# SMP_Project_2.net
KiCad netlist of a schematic drawn in EasyEDA Pro
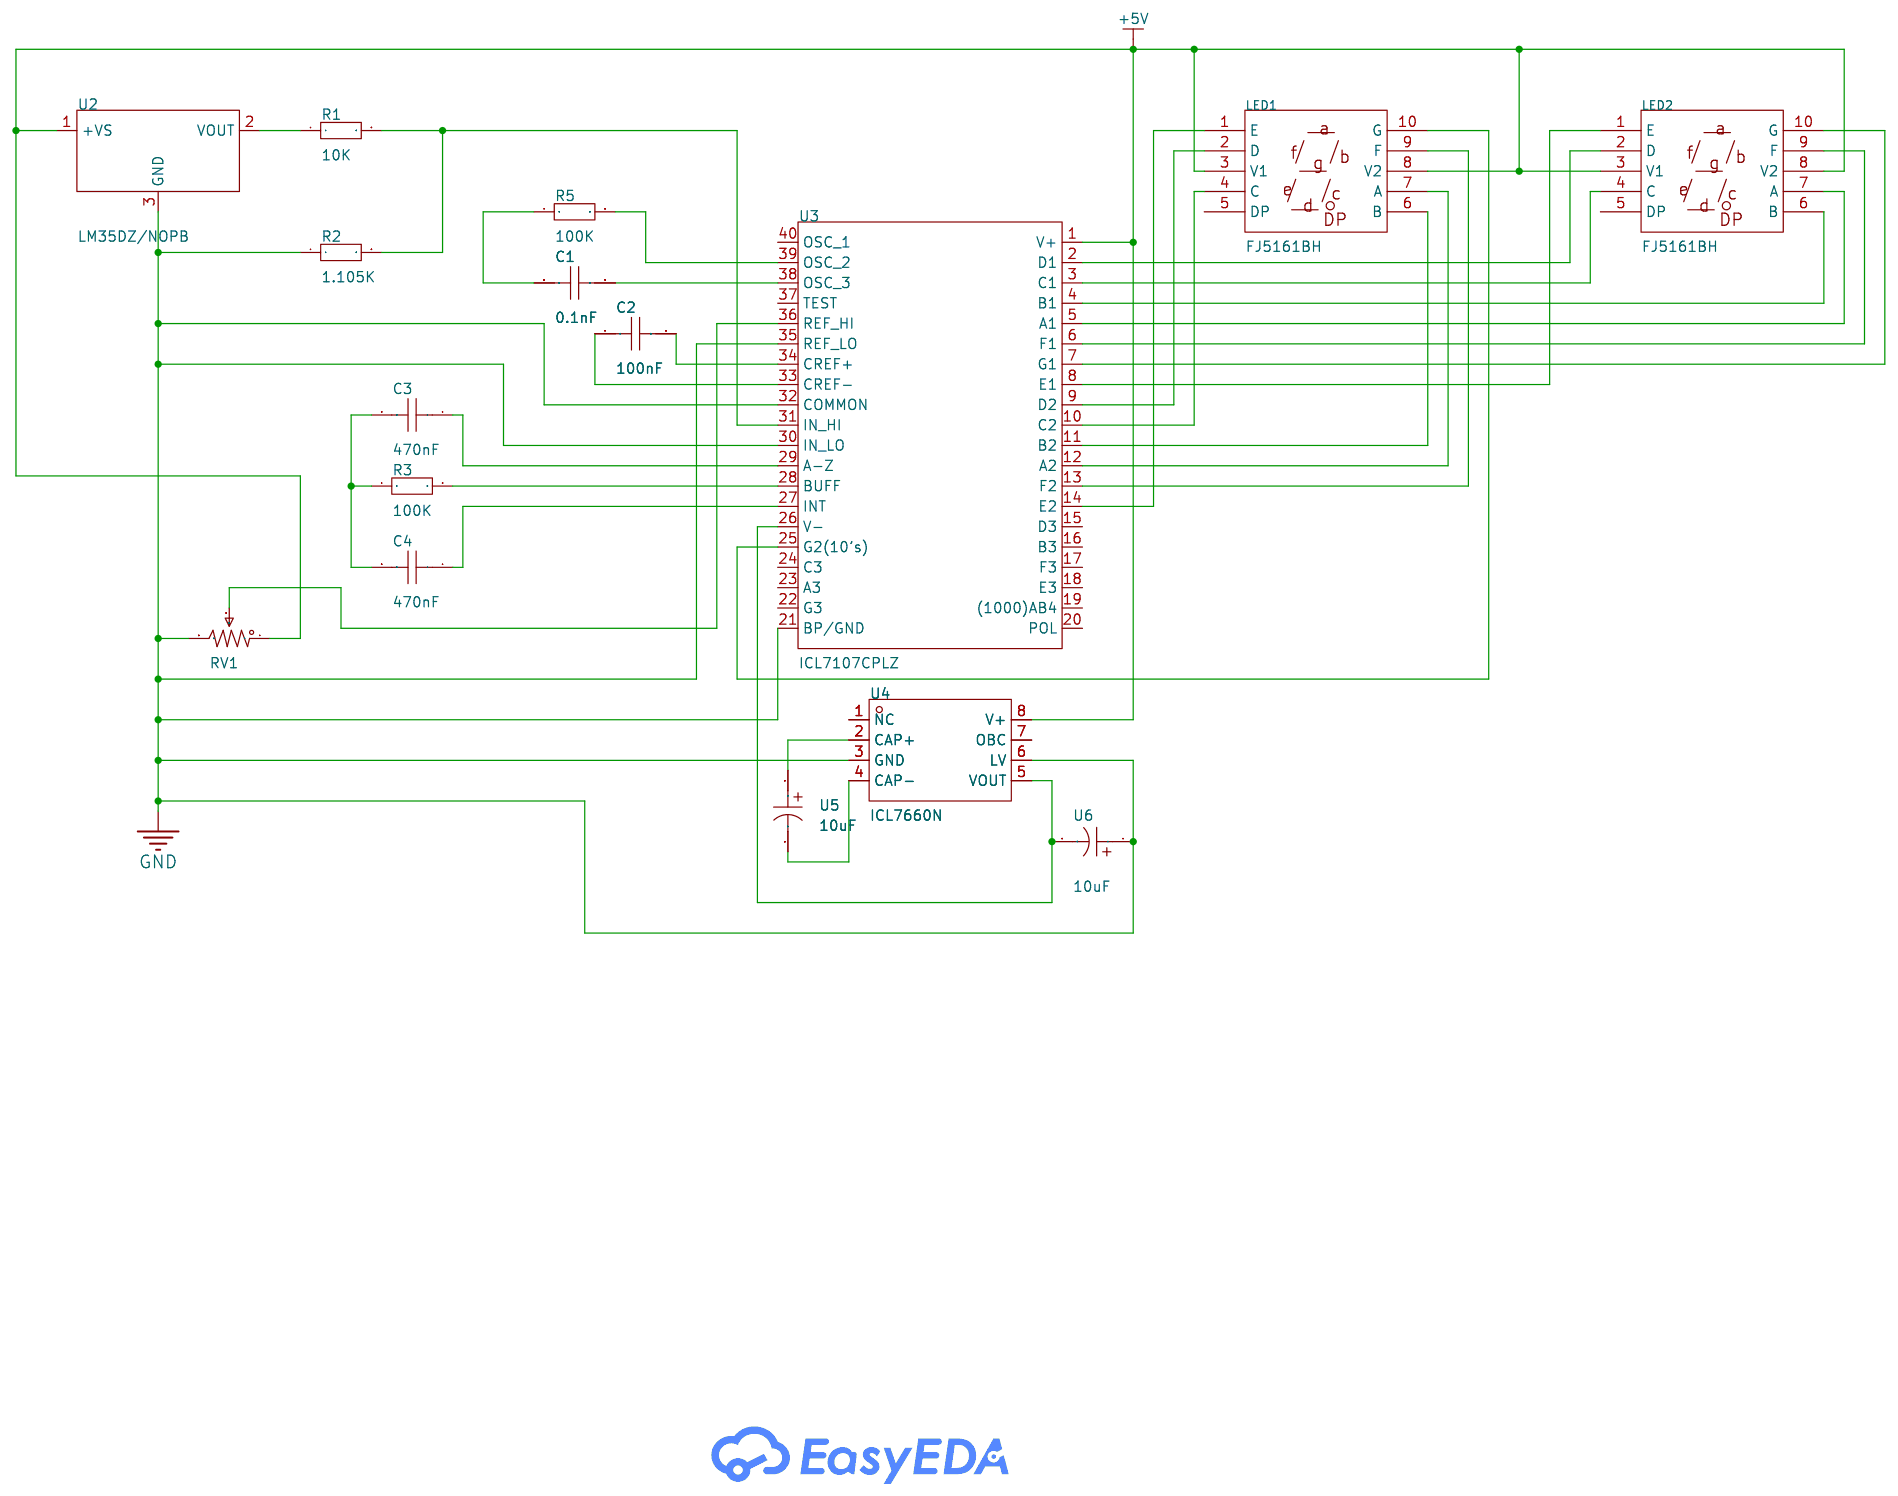
[diagram p0: schematic sheet]

(export (version "E")
  (design (tool "Eeschema 10.0.6"))
  (components
    (comp (ref "C1")
      (value "0.1nF")
      (footprint "easyedapro:C0805")
      (libsource (lib "easyedapro") (part "CAP"))
    )
    (comp (ref "C2")
      (value "100nF")
      (footprint "easyedapro:C0805")
      (libsource (lib "easyedapro") (part "CAP"))
    )
    (comp (ref "C3")
      (value "470nF")
      (footprint "easyedapro:C0805")
      (libsource (lib "easyedapro") (part "CAP"))
    )
    (comp (ref "C4")
      (value "470nF")
      (footprint "easyedapro:C0805")
      (libsource (lib "easyedapro") (part "CAP"))
    )
    (comp (ref "LED1")
      (value "FJ5161BH")
      (footprint "easyedapro:LED-SEG-TH_FJ5161BH")
      (fields (field (name "Manufacturer") "志浩"))
      (libsource (lib "easyedapro") (part "FJ5161BH"))
    )
    (comp (ref "LED2")
      (value "FJ5161BH")
      (footprint "easyedapro:LED-SEG-TH_FJ5161BH")
      (fields (field (name "Manufacturer") "志浩"))
      (libsource (lib "easyedapro") (part "FJ5161BH"))
    )
    (comp (ref "R1") (value "10K") (footprint "easyedapro:R0603") (libsource (lib "easyedapro") (part "Res")))
    (comp (ref "R2")
      (value "1.105K")
      (footprint "easyedapro:R0603")
      (libsource (lib "easyedapro") (part "Res"))
    )
    (comp (ref "R3")
      (value "100K")
      (footprint "easyedapro:R0603")
      (libsource (lib "easyedapro") (part "Res"))
    )
    (comp (ref "R5")
      (value "100K")
      (footprint "easyedapro:R0603")
      (libsource (lib "easyedapro") (part "Res"))
    )
    (comp (ref "RV1")
      (value "1kΩ")
      (footprint "easyedapro:RES-ADJ-TH_3P-L10.0-W10.0-P2.50-BL-BS")
      (fields (field (name "Manufacturer Part") "3296W-1-102") (field (name "Manufacturer") "BOCHEN(博晨)"))
      (libsource (lib "easyedapro") (part "3296W-1-102"))
    )
    (comp (ref "U2")
      (value "LM35DZ/NOPB")
      (footprint "easyedapro:TO-92-3_L4.9-W3.7-P1.27-L")
      (fields (field (name "Manufacturer") "TI(德州仪器)"))
      (libsource (lib "easyedapro") (part "LM35DZ"))
    )
    (comp (ref "U3")
      (value "ICL7107CPLZ")
      (footprint "easyedapro:DIP-40_L52.3-W13.9-P2.54-LS15.2-BL")
      (fields (field (name "Manufacturer") "RENESAS(瑞萨)/IDT"))
      (libsource (lib "easyedapro") (part "ICL7107CPLZ_C1520744"))
    )
    (comp (ref "U4")
      (value "ICL7660N")
      (footprint "easyedapro:DIP-8_L9.4-W6.4-P2.54-LS9.1-BL")
      (fields (field (name "Manufacturer") "HGSEMI(华冠)"))
      (libsource (lib "easyedapro") (part "ICL7660N"))
    )
    (comp (ref "U5")
      (value "10uF")
      (footprint "easyedapro:CAP-TH_BD10.0-P5.00-D0.6-FD")
      (libsource (lib "easyedapro") (part "10UF_400V"))
    )
    (comp (ref "U6")
      (value "10uF")
      (footprint "easyedapro:CAP-TH_BD10.0-P5.00-D0.6-FD")
      (libsource (lib "easyedapro") (part "10UF_400V"))
    )
  )
  (nets
    (net (code "1") (name "+5V") (class "Default")
      (node (ref "LED1") (pin "3") (pinfunction "V1_3") (pintype "input"))
      (node (ref "LED1") (pin "8") (pinfunction "V2_8") (pintype "input"))
      (node (ref "LED2") (pin "3") (pinfunction "V1_3") (pintype "input"))
      (node (ref "LED2") (pin "8") (pinfunction "V2_8") (pintype "input"))
      (node (ref "RV1") (pin "1") (pinfunction "1_1") (pintype "input"))
      (node (ref "U2") (pin "1") (pinfunction "+VS_1") (pintype "unspecified"))
      (node (ref "U3") (pin "1") (pinfunction "V+_1") (pintype "unspecified"))
      (node (ref "U4") (pin "8") (pinfunction "V+_8") (pintype "unspecified"))
    )
    (net (code "2") (name "GND") (class "Default")
      (node (ref "R2") (pin "1") (pinfunction "1_1") (pintype "input"))
      (node (ref "RV1") (pin "3") (pinfunction "3_3") (pintype "input"))
      (node (ref "U2") (pin "3") (pinfunction "GND_3") (pintype "unspecified"))
      (node (ref "U3") (pin "21") (pinfunction "BP/GND_21") (pintype "unspecified"))
      (node (ref "U3") (pin "30") (pinfunction "IN_LO_30") (pintype "unspecified"))
      (node (ref "U3") (pin "32") (pinfunction "COMMON_32") (pintype "unspecified"))
      (node (ref "U3") (pin "35") (pinfunction "REF_LO_35") (pintype "unspecified"))
      (node (ref "U4") (pin "3") (pinfunction "GND_3") (pintype "unspecified"))
      (node (ref "U4") (pin "6") (pinfunction "LV_6") (pintype "unspecified"))
      (node (ref "U6") (pin "1") (pinfunction "1_1") (pintype "input"))
    )
    (net (code "3") (name "Net-(C1-Pad2)") (class "Default")
      (node (ref "C1") (pin "2") (pinfunction "2_2") (pintype "input"))
      (node (ref "R5") (pin "1") (pinfunction "1_1") (pintype "input"))
    )
    (net (code "4") (name "Net-(C3-Pad2)") (class "Default")
      (node (ref "C3") (pin "2") (pinfunction "2_2") (pintype "input"))
      (node (ref "C4") (pin "2") (pinfunction "2_2") (pintype "input"))
      (node (ref "R3") (pin "1") (pinfunction "1_1") (pintype "input"))
    )
    (net (code "5") (name "Net-(LED1-A)") (class "Default")
      (node (ref "LED1") (pin "7") (pinfunction "A_7") (pintype "input"))
      (node (ref "U3") (pin "12") (pinfunction "A2_12") (pintype "unspecified"))
    )
    (net (code "6") (name "Net-(LED1-B)") (class "Default")
      (node (ref "LED1") (pin "6") (pinfunction "B_6") (pintype "input"))
      (node (ref "U3") (pin "11") (pinfunction "B2_11") (pintype "unspecified"))
    )
    (net (code "7") (name "Net-(LED1-C)") (class "Default")
      (node (ref "LED1") (pin "4") (pinfunction "C_4") (pintype "input"))
      (node (ref "U3") (pin "10") (pinfunction "C2_10") (pintype "unspecified"))
    )
    (net (code "8") (name "Net-(LED1-D)") (class "Default")
      (node (ref "LED1") (pin "2") (pinfunction "D_2") (pintype "input"))
      (node (ref "U3") (pin "9") (pinfunction "D2_9") (pintype "unspecified"))
    )
    (net (code "9") (name "Net-(LED1-E)") (class "Default")
      (node (ref "LED1") (pin "1") (pinfunction "E_1") (pintype "input"))
      (node (ref "U3") (pin "14") (pinfunction "E2_14") (pintype "unspecified"))
    )
    (net (code "10") (name "Net-(LED1-F)") (class "Default")
      (node (ref "LED1") (pin "9") (pinfunction "F_9") (pintype "input"))
      (node (ref "U3") (pin "13") (pinfunction "F2_13") (pintype "unspecified"))
    )
    (net (code "11") (name "Net-(LED1-G)") (class "Default")
      (node (ref "LED1") (pin "10") (pinfunction "G_10") (pintype "input"))
      (node (ref "U3") (pin "25") (pinfunction "G2(10’s)_25") (pintype "unspecified"))
    )
    (net (code "12") (name "Net-(LED2-A)") (class "Default")
      (node (ref "LED2") (pin "7") (pinfunction "A_7") (pintype "input"))
      (node (ref "U3") (pin "5") (pinfunction "A1_5") (pintype "unspecified"))
    )
    (net (code "13") (name "Net-(LED2-B)") (class "Default")
      (node (ref "LED2") (pin "6") (pinfunction "B_6") (pintype "input"))
      (node (ref "U3") (pin "4") (pinfunction "B1_4") (pintype "unspecified"))
    )
    (net (code "14") (name "Net-(LED2-C)") (class "Default")
      (node (ref "LED2") (pin "4") (pinfunction "C_4") (pintype "input"))
      (node (ref "U3") (pin "3") (pinfunction "C1_3") (pintype "unspecified"))
    )
    (net (code "15") (name "Net-(LED2-D)") (class "Default")
      (node (ref "LED2") (pin "2") (pinfunction "D_2") (pintype "input"))
      (node (ref "U3") (pin "2") (pinfunction "D1_2") (pintype "unspecified"))
    )
    (net (code "16") (name "Net-(LED2-E)") (class "Default")
      (node (ref "LED2") (pin "1") (pinfunction "E_1") (pintype "input"))
      (node (ref "U3") (pin "8") (pinfunction "E1_8") (pintype "unspecified"))
    )
    (net (code "17") (name "Net-(LED2-F)") (class "Default")
      (node (ref "LED2") (pin "9") (pinfunction "F_9") (pintype "input"))
      (node (ref "U3") (pin "6") (pinfunction "F1_6") (pintype "unspecified"))
    )
    (net (code "18") (name "Net-(LED2-G)") (class "Default")
      (node (ref "LED2") (pin "10") (pinfunction "G_10") (pintype "input"))
      (node (ref "U3") (pin "7") (pinfunction "G1_7") (pintype "unspecified"))
    )
    (net (code "19") (name "Net-(U2-VOUT)") (class "Default")
      (node (ref "R1") (pin "1") (pinfunction "1_1") (pintype "input"))
      (node (ref "U2") (pin "2") (pinfunction "VOUT_2") (pintype "unspecified"))
    )
    (net (code "20") (name "Net-(U3-A-Z)") (class "Default")
      (node (ref "C3") (pin "1") (pinfunction "1_1") (pintype "input"))
      (node (ref "U3") (pin "29") (pinfunction "A-Z_29") (pintype "unspecified"))
    )
    (net (code "21") (name "Net-(U3-BUFF)") (class "Default")
      (node (ref "R3") (pin "2") (pinfunction "2_2") (pintype "input"))
      (node (ref "U3") (pin "28") (pinfunction "BUFF_28") (pintype "unspecified"))
    )
    (net (code "22") (name "Net-(U3-CREF+)") (class "Default")
      (node (ref "C2") (pin "2") (pinfunction "2_2") (pintype "input"))
      (node (ref "U3") (pin "34") (pinfunction "CREF+_34") (pintype "unspecified"))
    )
    (net (code "23") (name "Net-(U3-CREF-)") (class "Default")
      (node (ref "C2") (pin "1") (pinfunction "1_1") (pintype "input"))
      (node (ref "U3") (pin "33") (pinfunction "CREF-_33") (pintype "unspecified"))
    )
    (net (code "24") (name "Net-(U3-INT)") (class "Default")
      (node (ref "C4") (pin "1") (pinfunction "1_1") (pintype "input"))
      (node (ref "U3") (pin "27") (pinfunction "INT_27") (pintype "unspecified"))
    )
    (net (code "25") (name "Net-(U3-IN_HI)") (class "Default")
      (node (ref "R1") (pin "2") (pinfunction "2_2") (pintype "input"))
      (node (ref "R2") (pin "2") (pinfunction "2_2") (pintype "input"))
      (node (ref "U3") (pin "31") (pinfunction "IN_HI_31") (pintype "unspecified"))
    )
    (net (code "26") (name "Net-(U3-OSC_2)") (class "Default")
      (node (ref "R5") (pin "2") (pinfunction "2_2") (pintype "input"))
      (node (ref "U3") (pin "39") (pinfunction "OSC_2_39") (pintype "unspecified"))
    )
    (net (code "27") (name "Net-(U3-OSC_3)") (class "Default")
      (node (ref "C1") (pin "1") (pinfunction "1_1") (pintype "input"))
      (node (ref "U3") (pin "38") (pinfunction "OSC_3_38") (pintype "unspecified"))
    )
    (net (code "28") (name "Net-(U3-REF_HI)") (class "Default")
      (node (ref "RV1") (pin "2") (pinfunction "2_2") (pintype "input"))
      (node (ref "U3") (pin "36") (pinfunction "REF_HI_36") (pintype "unspecified"))
    )
    (net (code "29") (name "Net-(U3-V-)") (class "Default")
      (node (ref "U3") (pin "26") (pinfunction "V-_26") (pintype "unspecified"))
      (node (ref "U4") (pin "5") (pinfunction "VOUT_5") (pintype "unspecified"))
      (node (ref "U6") (pin "2") (pinfunction "2_2") (pintype "input"))
    )
    (net (code "30") (name "Net-(U4-CAP+)") (class "Default")
      (node (ref "U4") (pin "2") (pinfunction "CAP+_2") (pintype "unspecified"))
      (node (ref "U5") (pin "1") (pinfunction "1_1") (pintype "input"))
    )
    (net (code "31") (name "Net-(U4-CAP-)") (class "Default")
      (node (ref "U4") (pin "4") (pinfunction "CAP-_4") (pintype "unspecified"))
      (node (ref "U5") (pin "2") (pinfunction "2_2") (pintype "input"))
    )
    (net (code "32") (name "unconnected-(LED1-DP-Pad5)") (class "Default")
      (node (ref "LED1") (pin "5") (pinfunction "DP_5") (pintype "input"))
    )
    (net (code "33") (name "unconnected-(LED2-DP-Pad5)") (class "Default")
      (node (ref "LED2") (pin "5") (pinfunction "DP_5") (pintype "input"))
    )
    (net (code "34") (name "unconnected-(U3-(1000)AB4-Pad19)") (class "Default")
      (node (ref "U3") (pin "19") (pinfunction "(1000)AB4_19") (pintype "unspecified"))
    )
    (net (code "35") (name "unconnected-(U3-A3-Pad23)") (class "Default")
      (node (ref "U3") (pin "23") (pinfunction "A3_23") (pintype "unspecified"))
    )
    (net (code "36") (name "unconnected-(U3-B3-Pad16)") (class "Default")
      (node (ref "U3") (pin "16") (pinfunction "B3_16") (pintype "unspecified"))
    )
    (net (code "37") (name "unconnected-(U3-C3-Pad24)") (class "Default")
      (node (ref "U3") (pin "24") (pinfunction "C3_24") (pintype "unspecified"))
    )
    (net (code "38") (name "unconnected-(U3-D3-Pad15)") (class "Default")
      (node (ref "U3") (pin "15") (pinfunction "D3_15") (pintype "unspecified"))
    )
    (net (code "39") (name "unconnected-(U3-E3-Pad18)") (class "Default")
      (node (ref "U3") (pin "18") (pinfunction "E3_18") (pintype "unspecified"))
    )
    (net (code "40") (name "unconnected-(U3-F3-Pad17)") (class "Default")
      (node (ref "U3") (pin "17") (pinfunction "F3_17") (pintype "unspecified"))
    )
    (net (code "41") (name "unconnected-(U3-G3-Pad22)") (class "Default")
      (node (ref "U3") (pin "22") (pinfunction "G3_22") (pintype "unspecified"))
    )
    (net (code "42") (name "unconnected-(U3-OSC_1-Pad40)") (class "Default")
      (node (ref "U3") (pin "40") (pinfunction "OSC_1_40") (pintype "unspecified"))
    )
    (net (code "43") (name "unconnected-(U3-POL-Pad20)") (class "Default")
      (node (ref "U3") (pin "20") (pinfunction "POL_20") (pintype "unspecified"))
    )
    (net (code "44") (name "unconnected-(U3-TEST-Pad37)") (class "Default")
      (node (ref "U3") (pin "37") (pinfunction "TEST_37") (pintype "unspecified"))
    )
    (net (code "45") (name "unconnected-(U4-NC-Pad1)") (class "Default")
      (node (ref "U4") (pin "1") (pinfunction "NC_1") (pintype "unspecified"))
    )
    (net (code "46") (name "unconnected-(U4-OBC-Pad7)") (class "Default")
      (node (ref "U4") (pin "7") (pinfunction "OBC_7") (pintype "unspecified"))
    )
  )
)
